# SCH.net
KiCad netlist of a schematic drawn in Altium Designer
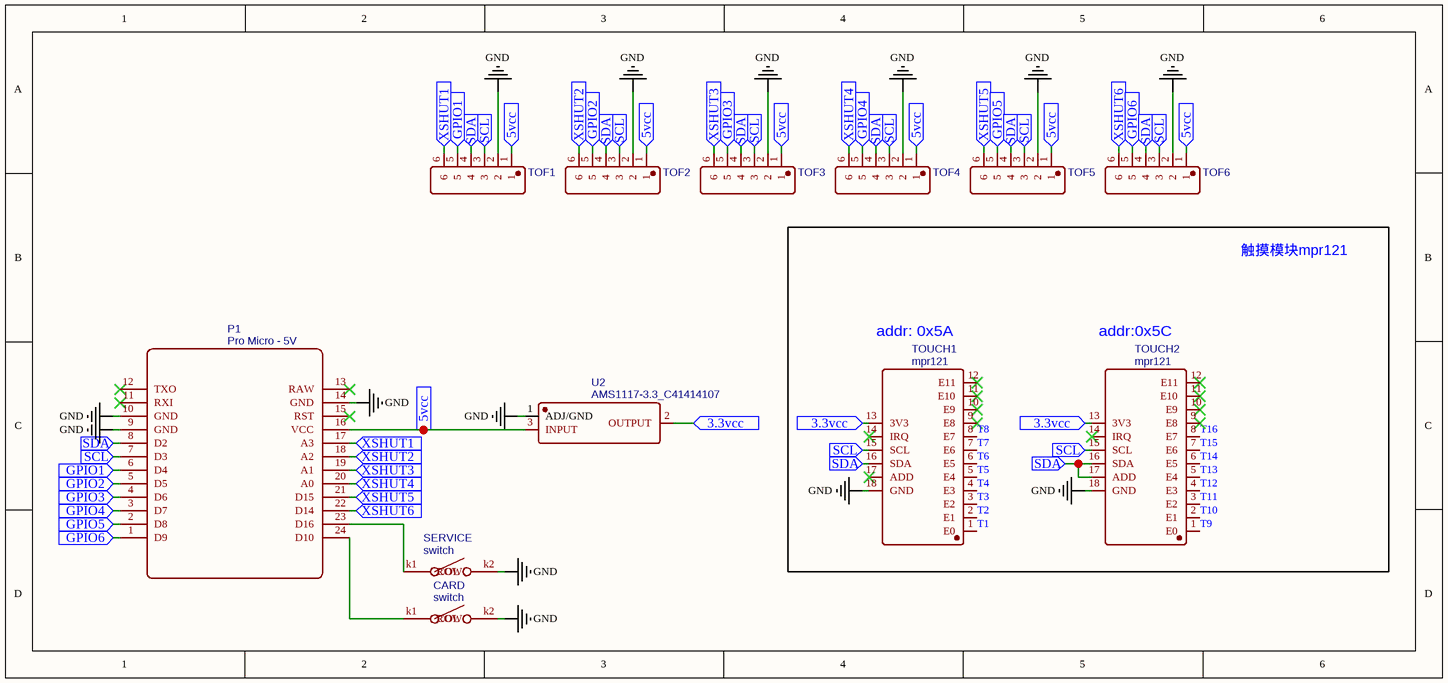
[diagram p0: SCH.schdoc]

(export (version "E")
  (design (tool "Eeschema 10.0.6"))
  (components
    (comp (ref "CARD")
      (value "switch")
      (fields (field (name "CONTRIBUTOR") "wnyr"))
      (libsource (lib "altium-import") (part "root_0_switch_"))
    )
    (comp (ref "P1")
      (value "Pro Micro - 5V")
      (libsource (lib "altium-import") (part "root_0_Pro Micro - 5V_"))
    )
    (comp (ref "SERVICE")
      (value "switch")
      (fields (field (name "CONTRIBUTOR") "wnyr"))
      (libsource (lib "altium-import") (part "root_0_switch_"))
    )
    (comp (ref "TOF1")
      (value "双塑单排排针6PIN2.54间距")
      (fields (field (name "CONTRIBUTOR") "lcsc"))
      (libsource (lib "altium-import") (part "root_3_双塑单排排针6PIN2.54间距_"))
    )
    (comp (ref "TOF2")
      (value "双塑单排排针6PIN2.54间距")
      (fields (field (name "CONTRIBUTOR") "lcsc"))
      (libsource (lib "altium-import") (part "root_3_双塑单排排针6PIN2.54间距_"))
    )
    (comp (ref "TOF3")
      (value "双塑单排排针6PIN2.54间距")
      (fields (field (name "CONTRIBUTOR") "lcsc"))
      (libsource (lib "altium-import") (part "root_3_双塑单排排针6PIN2.54间距_"))
    )
    (comp (ref "TOF4")
      (value "双塑单排排针6PIN2.54间距")
      (fields (field (name "CONTRIBUTOR") "lcsc"))
      (libsource (lib "altium-import") (part "root_3_双塑单排排针6PIN2.54间距_"))
    )
    (comp (ref "TOF5")
      (value "双塑单排排针6PIN2.54间距")
      (fields (field (name "CONTRIBUTOR") "lcsc"))
      (libsource (lib "altium-import") (part "root_3_双塑单排排针6PIN2.54间距_"))
    )
    (comp (ref "TOF6")
      (value "双塑单排排针6PIN2.54间距")
      (fields (field (name "CONTRIBUTOR") "lcsc"))
      (libsource (lib "altium-import") (part "root_3_双塑单排排针6PIN2.54间距_"))
    )
    (comp (ref "TOUCH1")
      (value "mpr121")
      (fields (field (name "CONTRIBUTOR") "goodwood"))
      (libsource (lib "altium-import") (part "root_2_mpr121_"))
    )
    (comp (ref "TOUCH2")
      (value "mpr121")
      (fields (field (name "CONTRIBUTOR") "goodwood"))
      (libsource (lib "altium-import") (part "root_2_mpr121_"))
    )
    (comp (ref "U2")
      (value "AMS1117-3.3_C41414107")
      (fields
        (field (name "MANUFACTURER") "YONGYUTAI(永裕泰)")
        (field (name "MANUFACTURER PART") "AMS1117-3.3")
        (field (name "CONTRIBUTOR") "lcsc")
      )
      (libsource (lib "altium-import") (part "root_0_AMS1117-3.3_C41414107_"))
    )
  )
  (nets
    (net (code "1") (name "/3.3vcc") (class "Default")
      (node (ref "TOUCH1") (pin "13") (pinfunction "3V3_13") (pintype "passive"))
      (node (ref "TOUCH2") (pin "13") (pinfunction "3V3_13") (pintype "passive"))
      (node (ref "U2") (pin "2") (pinfunction "OUTPUT_2") (pintype "passive"))
    )
    (net (code "2") (name "/5vcc") (class "Default")
      (node (ref "P1") (pin "16") (pinfunction "VCC_16") (pintype "passive"))
      (node (ref "TOF1") (pin "1") (pinfunction "1_1") (pintype "passive"))
      (node (ref "TOF2") (pin "1") (pinfunction "1_1") (pintype "passive"))
      (node (ref "TOF3") (pin "1") (pinfunction "1_1") (pintype "passive"))
      (node (ref "TOF4") (pin "1") (pinfunction "1_1") (pintype "passive"))
      (node (ref "TOF5") (pin "1") (pinfunction "1_1") (pintype "passive"))
      (node (ref "TOF6") (pin "1") (pinfunction "1_1") (pintype "passive"))
      (node (ref "U2") (pin "3") (pinfunction "INPUT_3") (pintype "passive"))
    )
    (net (code "3") (name "/GPIO1") (class "Default")
      (node (ref "P1") (pin "6") (pinfunction "D4_6") (pintype "passive"))
      (node (ref "TOF1") (pin "5") (pinfunction "5_5") (pintype "passive"))
    )
    (net (code "4") (name "/GPIO2") (class "Default")
      (node (ref "P1") (pin "5") (pinfunction "D5_5") (pintype "passive"))
      (node (ref "TOF2") (pin "5") (pinfunction "5_5") (pintype "passive"))
    )
    (net (code "5") (name "/GPIO3") (class "Default")
      (node (ref "P1") (pin "4") (pinfunction "D6_4") (pintype "passive"))
      (node (ref "TOF3") (pin "5") (pinfunction "5_5") (pintype "passive"))
    )
    (net (code "6") (name "/GPIO4") (class "Default")
      (node (ref "P1") (pin "3") (pinfunction "D7_3") (pintype "passive"))
      (node (ref "TOF4") (pin "5") (pinfunction "5_5") (pintype "passive"))
    )
    (net (code "7") (name "/GPIO5") (class "Default")
      (node (ref "P1") (pin "2") (pinfunction "D8_2") (pintype "passive"))
      (node (ref "TOF5") (pin "5") (pinfunction "5_5") (pintype "passive"))
    )
    (net (code "8") (name "/GPIO6") (class "Default")
      (node (ref "P1") (pin "1") (pinfunction "D9_1") (pintype "passive"))
      (node (ref "TOF6") (pin "5") (pinfunction "5_5") (pintype "passive"))
    )
    (net (code "9") (name "/SCL") (class "Default")
      (node (ref "P1") (pin "7") (pinfunction "D3_7") (pintype "passive"))
      (node (ref "TOF1") (pin "3") (pinfunction "3_3") (pintype "passive"))
      (node (ref "TOF2") (pin "3") (pinfunction "3_3") (pintype "passive"))
      (node (ref "TOF3") (pin "3") (pinfunction "3_3") (pintype "passive"))
      (node (ref "TOF4") (pin "3") (pinfunction "3_3") (pintype "passive"))
      (node (ref "TOF5") (pin "3") (pinfunction "3_3") (pintype "passive"))
      (node (ref "TOF6") (pin "3") (pinfunction "3_3") (pintype "passive"))
      (node (ref "TOUCH1") (pin "15") (pinfunction "SCL_15") (pintype "passive"))
      (node (ref "TOUCH2") (pin "15") (pinfunction "SCL_15") (pintype "passive"))
    )
    (net (code "10") (name "/SDA") (class "Default")
      (node (ref "P1") (pin "8") (pinfunction "D2_8") (pintype "passive"))
      (node (ref "TOF1") (pin "4") (pinfunction "4_4") (pintype "passive"))
      (node (ref "TOF2") (pin "4") (pinfunction "4_4") (pintype "passive"))
      (node (ref "TOF3") (pin "4") (pinfunction "4_4") (pintype "passive"))
      (node (ref "TOF4") (pin "4") (pinfunction "4_4") (pintype "passive"))
      (node (ref "TOF5") (pin "4") (pinfunction "4_4") (pintype "passive"))
      (node (ref "TOF6") (pin "4") (pinfunction "4_4") (pintype "passive"))
      (node (ref "TOUCH1") (pin "16") (pinfunction "SDA_16") (pintype "passive"))
      (node (ref "TOUCH2") (pin "16") (pinfunction "SDA_16") (pintype "passive"))
      (node (ref "TOUCH2") (pin "17") (pinfunction "ADD_17") (pintype "passive"))
    )
    (net (code "11") (name "/T1") (class "Default")
      (node (ref "TOUCH1") (pin "1") (pinfunction "E0_1") (pintype "passive"))
    )
    (net (code "12") (name "/T2") (class "Default")
      (node (ref "TOUCH1") (pin "2") (pinfunction "E1_2") (pintype "passive"))
    )
    (net (code "13") (name "/T3") (class "Default")
      (node (ref "TOUCH1") (pin "3") (pinfunction "E2_3") (pintype "passive"))
    )
    (net (code "14") (name "/T4") (class "Default")
      (node (ref "TOUCH1") (pin "4") (pinfunction "E3_4") (pintype "passive"))
    )
    (net (code "15") (name "/T5") (class "Default")
      (node (ref "TOUCH1") (pin "5") (pinfunction "E4_5") (pintype "passive"))
    )
    (net (code "16") (name "/T6") (class "Default")
      (node (ref "TOUCH1") (pin "6") (pinfunction "E5_6") (pintype "passive"))
    )
    (net (code "17") (name "/T7") (class "Default")
      (node (ref "TOUCH1") (pin "7") (pinfunction "E6_7") (pintype "passive"))
    )
    (net (code "18") (name "/T8") (class "Default")
      (node (ref "TOUCH1") (pin "8") (pinfunction "E7_8") (pintype "passive"))
    )
    (net (code "19") (name "/T9") (class "Default")
      (node (ref "TOUCH2") (pin "1") (pinfunction "E0_1") (pintype "passive"))
    )
    (net (code "20") (name "/T10") (class "Default")
      (node (ref "TOUCH2") (pin "2") (pinfunction "E1_2") (pintype "passive"))
    )
    (net (code "21") (name "/T11") (class "Default")
      (node (ref "TOUCH2") (pin "3") (pinfunction "E2_3") (pintype "passive"))
    )
    (net (code "22") (name "/T12") (class "Default")
      (node (ref "TOUCH2") (pin "4") (pinfunction "E3_4") (pintype "passive"))
    )
    (net (code "23") (name "/T13") (class "Default")
      (node (ref "TOUCH2") (pin "5") (pinfunction "E4_5") (pintype "passive"))
    )
    (net (code "24") (name "/T14") (class "Default")
      (node (ref "TOUCH2") (pin "6") (pinfunction "E5_6") (pintype "passive"))
    )
    (net (code "25") (name "/T15") (class "Default")
      (node (ref "TOUCH2") (pin "7") (pinfunction "E6_7") (pintype "passive"))
    )
    (net (code "26") (name "/T16") (class "Default")
      (node (ref "TOUCH2") (pin "8") (pinfunction "E7_8") (pintype "passive"))
    )
    (net (code "27") (name "/XSHUT1") (class "Default")
      (node (ref "P1") (pin "17") (pinfunction "A3_17") (pintype "passive"))
      (node (ref "TOF1") (pin "6") (pinfunction "6_6") (pintype "passive"))
    )
    (net (code "28") (name "/XSHUT2") (class "Default")
      (node (ref "P1") (pin "18") (pinfunction "A2_18") (pintype "passive"))
      (node (ref "TOF2") (pin "6") (pinfunction "6_6") (pintype "passive"))
    )
    (net (code "29") (name "/XSHUT3") (class "Default")
      (node (ref "P1") (pin "19") (pinfunction "A1_19") (pintype "passive"))
      (node (ref "TOF3") (pin "6") (pinfunction "6_6") (pintype "passive"))
    )
    (net (code "30") (name "/XSHUT4") (class "Default")
      (node (ref "P1") (pin "20") (pinfunction "A0_20") (pintype "passive"))
      (node (ref "TOF4") (pin "6") (pinfunction "6_6") (pintype "passive"))
    )
    (net (code "31") (name "/XSHUT5") (class "Default")
      (node (ref "P1") (pin "21") (pinfunction "D15_21") (pintype "passive"))
      (node (ref "TOF5") (pin "6") (pinfunction "6_6") (pintype "passive"))
    )
    (net (code "32") (name "/XSHUT6") (class "Default")
      (node (ref "P1") (pin "22") (pinfunction "D14_22") (pintype "passive"))
      (node (ref "TOF6") (pin "6") (pinfunction "6_6") (pintype "passive"))
    )
    (net (code "33") (name "GND") (class "Default")
      (node (ref "CARD") (pin "k2") (pinfunction "ROW_k2") (pintype "passive"))
      (node (ref "P1") (pin "10") (pinfunction "GND_10") (pintype "passive"))
      (node (ref "P1") (pin "14") (pinfunction "GND_14") (pintype "passive"))
      (node (ref "P1") (pin "9") (pinfunction "GND_9") (pintype "passive"))
      (node (ref "SERVICE") (pin "k2") (pinfunction "ROW_k2") (pintype "passive"))
      (node (ref "TOF1") (pin "2") (pinfunction "2_2") (pintype "passive"))
      (node (ref "TOF2") (pin "2") (pinfunction "2_2") (pintype "passive"))
      (node (ref "TOF3") (pin "2") (pinfunction "2_2") (pintype "passive"))
      (node (ref "TOF4") (pin "2") (pinfunction "2_2") (pintype "passive"))
      (node (ref "TOF5") (pin "2") (pinfunction "2_2") (pintype "passive"))
      (node (ref "TOF6") (pin "2") (pinfunction "2_2") (pintype "passive"))
      (node (ref "TOUCH1") (pin "18") (pinfunction "GND_18") (pintype "passive"))
      (node (ref "TOUCH2") (pin "18") (pinfunction "GND_18") (pintype "passive"))
      (node (ref "U2") (pin "1") (pinfunction "ADJ/GND_1") (pintype "passive"))
    )
    (net (code "34") (name "Net-(CARD-COL)") (class "Default")
      (node (ref "CARD") (pin "k1") (pinfunction "COL_k1") (pintype "passive"))
      (node (ref "P1") (pin "24") (pinfunction "D10_24") (pintype "passive"))
    )
    (net (code "35") (name "Net-(P1-D16)") (class "Default")
      (node (ref "P1") (pin "23") (pinfunction "D16_23") (pintype "passive"))
      (node (ref "SERVICE") (pin "k1") (pinfunction "COL_k1") (pintype "passive"))
    )
    (net (code "36") (name "unconnected-(P1-RAW-Pad13)") (class "Default")
      (node (ref "P1") (pin "13") (pinfunction "RAW_13") (pintype "passive+no_connect"))
    )
    (net (code "37") (name "unconnected-(P1-RST-Pad15)") (class "Default")
      (node (ref "P1") (pin "15") (pinfunction "RST_15") (pintype "passive+no_connect"))
    )
    (net (code "38") (name "unconnected-(P1-RXI-Pad11)") (class "Default")
      (node (ref "P1") (pin "11") (pinfunction "RXI_11") (pintype "passive+no_connect"))
    )
    (net (code "39") (name "unconnected-(P1-TXO-Pad12)") (class "Default")
      (node (ref "P1") (pin "12") (pinfunction "TXO_12") (pintype "passive+no_connect"))
    )
    (net (code "40") (name "unconnected-(TOUCH1-ADD-Pad17)") (class "Default")
      (node (ref "TOUCH1") (pin "17") (pinfunction "ADD_17") (pintype "passive+no_connect"))
    )
    (net (code "41") (name "unconnected-(TOUCH1-E8-Pad9)") (class "Default")
      (node (ref "TOUCH1") (pin "9") (pinfunction "E8_9") (pintype "passive+no_connect"))
    )
    (net (code "42") (name "unconnected-(TOUCH1-E9-Pad10)") (class "Default")
      (node (ref "TOUCH1") (pin "10") (pinfunction "E9_10") (pintype "passive+no_connect"))
    )
    (net (code "43") (name "unconnected-(TOUCH1-E10-Pad11)") (class "Default")
      (node (ref "TOUCH1") (pin "11") (pinfunction "E10_11") (pintype "passive+no_connect"))
    )
    (net (code "44") (name "unconnected-(TOUCH1-E11-Pad12)") (class "Default")
      (node (ref "TOUCH1") (pin "12") (pinfunction "E11_12") (pintype "passive+no_connect"))
    )
    (net (code "45") (name "unconnected-(TOUCH1-IRQ-Pad14)") (class "Default")
      (node (ref "TOUCH1") (pin "14") (pinfunction "IRQ_14") (pintype "passive+no_connect"))
    )
    (net (code "46") (name "unconnected-(TOUCH2-E8-Pad9)") (class "Default")
      (node (ref "TOUCH2") (pin "9") (pinfunction "E8_9") (pintype "passive+no_connect"))
    )
    (net (code "47") (name "unconnected-(TOUCH2-E9-Pad10)") (class "Default")
      (node (ref "TOUCH2") (pin "10") (pinfunction "E9_10") (pintype "passive+no_connect"))
    )
    (net (code "48") (name "unconnected-(TOUCH2-E10-Pad11)") (class "Default")
      (node (ref "TOUCH2") (pin "11") (pinfunction "E10_11") (pintype "passive+no_connect"))
    )
    (net (code "49") (name "unconnected-(TOUCH2-E11-Pad12)") (class "Default")
      (node (ref "TOUCH2") (pin "12") (pinfunction "E11_12") (pintype "passive+no_connect"))
    )
    (net (code "50") (name "unconnected-(TOUCH2-IRQ-Pad14)") (class "Default")
      (node (ref "TOUCH2") (pin "14") (pinfunction "IRQ_14") (pintype "passive+no_connect"))
    )
  )
)
